# CH32V203CCT-WUI-R1-1v0.net
KiCad netlist of a schematic drawn in Altium Designer
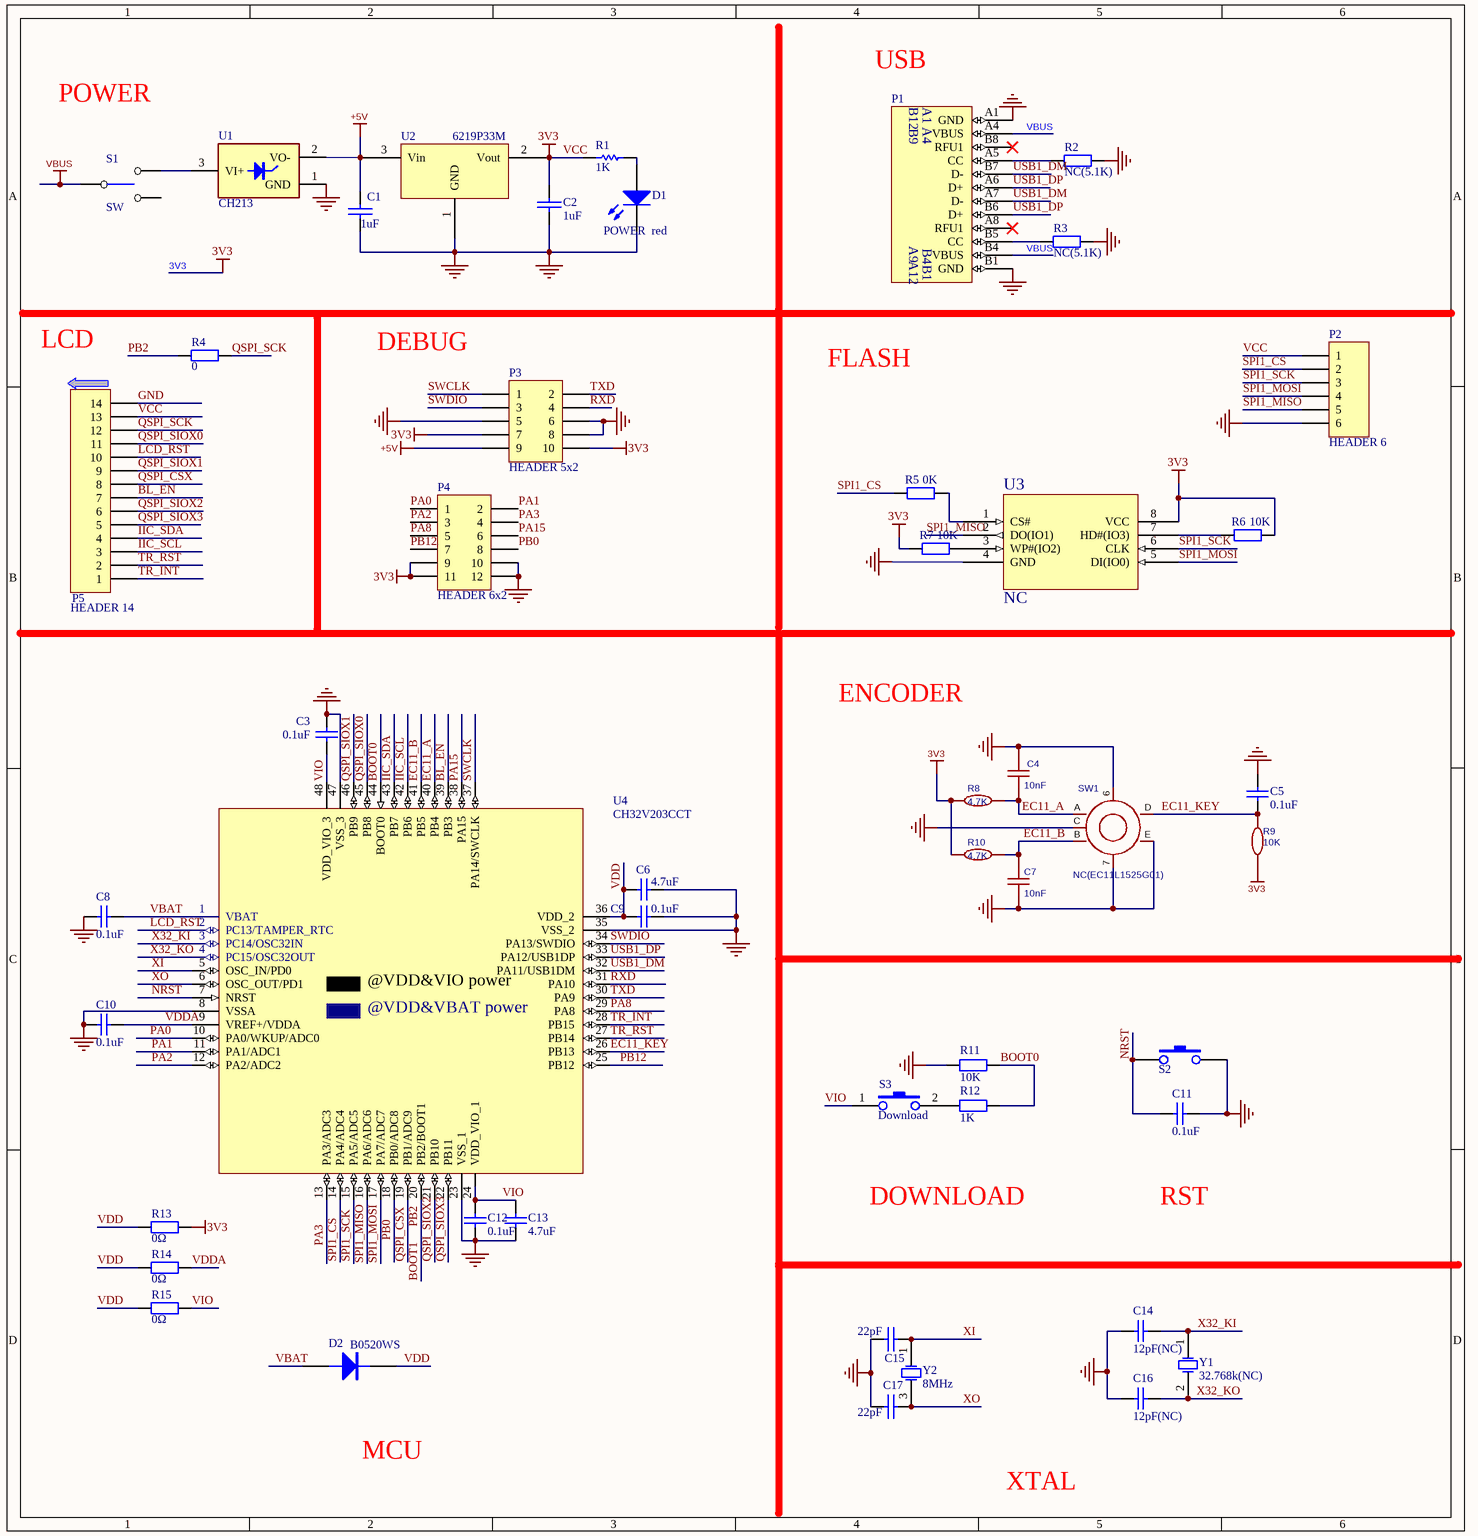
[diagram p0: CH32V203CCT-WUI-R1-1v0.SchDoc]

(export (version "E")
  (design (tool "Eeschema 10.0.6"))
  (components
    (comp (ref "C1")
      (value "1uF")
      (footprint "0402_C")
      (description "Capacitor")
      (libsource (lib "*") (part "CAP"))
    )
    (comp (ref "C2")
      (value "1uF")
      (footprint "0402_C")
      (description "Capacitor")
      (libsource (lib "*") (part "CAP"))
    )
    (comp (ref "C3")
      (value "0.1uF")
      (footprint "0402_C")
      (description "Capacitor")
      (fields (field (name "PUBLISHER") "Altium Limited"))
      (libsource (lib "*") (part "Cap"))
    )
    (comp (ref "C4")
      (value "10nF")
      (footprint "0402_C")
      (libsource (lib "altium-import") (part "root_1_CAP_0603_"))
    )
    (comp (ref "C5")
      (value "0.1uF")
      (footprint "0402_C")
      (description "Capacitor")
      (fields (field (name "PUBLISHER") "Altium Limited"))
      (libsource (lib "*") (part "Cap"))
    )
    (comp (ref "C6")
      (value "4.7uF")
      (footprint "0402_C")
      (description "Capacitor")
      (fields (field (name "PUBLISHER") "Altium Limited"))
      (libsource (lib "*") (part "Cap"))
    )
    (comp (ref "C7")
      (value "10nF")
      (footprint "0402_C")
      (libsource (lib "altium-import") (part "root_3_CAP_0603_"))
    )
    (comp (ref "C8")
      (value "0.1uF")
      (footprint "0402_C")
      (description "Capacitor")
      (fields (field (name "PUBLISHER") "Altium Limited"))
      (libsource (lib "*") (part "Cap"))
    )
    (comp (ref "C9")
      (value "0.1uF")
      (footprint "0402_C")
      (description "Capacitor")
      (fields (field (name "PUBLISHER") "Altium Limited"))
      (libsource (lib "*") (part "Cap"))
    )
    (comp (ref "C10")
      (value "0.1uF")
      (footprint "0402_C")
      (description "Capacitor")
      (fields (field (name "PUBLISHER") "Altium Limited"))
      (libsource (lib "*") (part "Cap"))
    )
    (comp (ref "C11")
      (value "0.1uF")
      (footprint "0402_C")
      (description "Capacitor")
      (fields (field (name "PUBLISHER") "Altium Limited"))
      (libsource (lib "*") (part "Cap"))
    )
    (comp (ref "C12")
      (value "0.1uF")
      (footprint "0402_C")
      (description "Capacitor")
      (fields (field (name "PUBLISHER") "Altium Limited"))
      (libsource (lib "*") (part "Cap"))
    )
    (comp (ref "C13")
      (value "4.7uF")
      (footprint "0402_C")
      (description "Capacitor")
      (fields (field (name "PUBLISHER") "Altium Limited"))
      (libsource (lib "*") (part "Cap"))
    )
    (comp (ref "C14")
      (value "12pF(NC)")
      (footprint "0402_C")
      (description "Capacitor")
      (fields (field (name "PUBLISHER") "Altium Limited"))
      (libsource (lib "*") (part "Cap"))
    )
    (comp (ref "C15")
      (value "22pF")
      (footprint "0402_C")
      (description "Capacitor")
      (libsource (lib "*") (part "CAP"))
    )
    (comp (ref "C16")
      (value "12pF(NC)")
      (footprint "0402_C")
      (description "Capacitor")
      (fields (field (name "PUBLISHER") "Altium Limited"))
      (libsource (lib "*") (part "Cap"))
    )
    (comp (ref "C17")
      (value "22pF")
      (footprint "0402_C")
      (description "Capacitor")
      (libsource (lib "*") (part "CAP"))
    )
    (comp (ref "D1")
      (value "POWER  red")
      (footprint "0603+")
      (description "Typical INFRARED GaAs LED")
      (fields (field (name "PUBLISHER") "Altium Limited"))
      (libsource (lib "*") (part "LED0"))
    )
    (comp (ref "D2")
      (value "B0520WS")
      (footprint "SOD-323")
      (description "Diode")
      (libsource (lib "*") (part "DIODE"))
    )
    (comp (ref "P1")
      (value "TYPE-C")
      (footprint "TYPE-C-Receptacle-2.0")
      (libsource (lib "*") (part "TYPE-C1"))
    )
    (comp (ref "P2")
      (value "HEADER 6")
      (footprint "SIP6-2.54mm")
      (description "Header, 6-Pin")
      (libsource (lib "wch_sch_others") (part "HEADER 6"))
    )
    (comp (ref "P3")
      (value "HEADER 5x2")
      (footprint "MYPCB:IDC10-2.54mm")
      (description "Header, 5-Pin, Dual row")
      (libsource (lib "wch_sch_others") (part "HEADER 5x2"))
    )
    (comp (ref "P4")
      (value "HEADER 6x2")
      (footprint "MYPCB:IDC12-2.54mm")
      (description "Header, 6-Pin, Dual row")
      (libsource (lib "wch_sch_others") (part "HEADER 6x2"))
    )
    (comp (ref "P5")
      (value "HEADER 14")
      (footprint "SIP14-2.54mm")
      (description "Header, 14-Pin")
      (libsource (lib "wch_sch_others") (part "HEADER 14"))
    )
    (comp (ref "R1")
      (value "1K")
      (footprint "0402")
      (description "Semiconductor Resistor")
      (fields (field (name "PUBLISHER") "Altium Limited"))
      (libsource (lib "*") (part "Res Semi"))
    )
    (comp (ref "R2")
      (value "NC(5.1K)")
      (footprint "0402")
      (description "Resistor")
      (libsource (lib "") (part "Res2_1"))
    )
    (comp (ref "R3")
      (value "NC(5.1K)")
      (footprint "0402")
      (description "Resistor")
      (libsource (lib "") (part "Res2_1"))
    )
    (comp (ref "R4")
      (value "0")
      (footprint "0402")
      (description "Resistor")
      (fields (field (name "PUBLISHER") "Altium Limited"))
      (libsource (lib "") (part "Res2_1"))
    )
    (comp (ref "R5")
      (value "0K")
      (footprint "0402")
      (description "Resistor")
      (fields (field (name "PUBLISHER") "Altium Limited"))
      (libsource (lib "*") (part "Res2"))
    )
    (comp (ref "R6")
      (value "10K")
      (footprint "0402")
      (description "Resistor")
      (fields (field (name "PUBLISHER") "Altium Limited"))
      (libsource (lib "*") (part "Res2"))
    )
    (comp (ref "R7")
      (value "10K")
      (footprint "0402")
      (description "Resistor")
      (fields (field (name "PUBLISHER") "Altium Limited"))
      (libsource (lib "*") (part "Res2"))
    )
    (comp (ref "R8")
      (value "4.7K")
      (footprint "0402")
      (libsource (lib "altium-import") (part "root_0_Res_0603_"))
    )
    (comp (ref "R9")
      (value "10K")
      (footprint "0402")
      (libsource (lib "altium-import") (part "root_3_Res_0603_"))
    )
    (comp (ref "R10")
      (value "4.7K")
      (footprint "0402")
      (libsource (lib "altium-import") (part "root_0_Res_0603_"))
    )
    (comp (ref "R11")
      (value "10K")
      (footprint "0402")
      (description "Resistor")
      (fields (field (name "PUBLISHER") "Altium Limited"))
      (libsource (lib "Miscellaneous Devices") (part "Res2"))
    )
    (comp (ref "R12")
      (value "1K")
      (footprint "0402")
      (description "Resistor")
      (fields (field (name "PUBLISHER") "Altium Limited"))
      (libsource (lib "Miscellaneous Devices") (part "Res2"))
    )
    (comp (ref "R13")
      (value "0Ω")
      (footprint "0402")
      (description "Resistor")
      (libsource (lib "Miscellaneous Devices") (part "Res2"))
    )
    (comp (ref "R14")
      (value "0Ω")
      (footprint "0402")
      (description "Resistor")
      (libsource (lib "Miscellaneous Devices") (part "Res2"))
    )
    (comp (ref "R15")
      (value "0Ω")
      (footprint "0402")
      (description "Resistor")
      (libsource (lib "Miscellaneous Devices") (part "Res2"))
    )
    (comp (ref "S1") (value "SW") (footprint "SW1") (libsource (lib "*") (part "SW")))
    (comp (ref "S2") (value "NRST") (footprint "贴片按键") (libsource (lib "*") (part "KEY")))
    (comp (ref "S3") (value "Download") (footprint "贴片按键") (libsource (lib "wch_sch_others") (part "KEY1")))
    (comp (ref "SW1")
      (value "NC(EC11L1525G01)")
      (footprint "SW-TH_ALPS_EC11L1525G01")
      (fields
        (field (name "MANUFACTURER") "ALPSALPINE(阿尔卑斯阿尔派)")
        (field (name "MANUFACTURERPART") "EC11L1525G01")
      )
      (libsource (lib "altium-import") (part "root_3_EC11L1525G01_"))
    )
    (comp (ref "U1")
      (value "CH213")
      (footprint "SOT-23-3")
      (description "Ideal Diode 5V*1A")
      (libsource (lib "CHXXX") (part "CH213E"))
    )
    (comp (ref "U2")
      (value "6219P33M")
      (footprint "SOT-23")
      (libsource (lib "wch_sch_others") (part "6219P33M"))
    )
    (comp (ref "U3")
      (value "NC")
      (footprint "SOIC-8_208mil")
      (libsource (lib "wch_sch_others") (part "W25Q32JV"))
    )
    (comp (ref "U4")
      (value "CH32V203CCT")
      (footprint "LQFP48")
      (description "RISC-V MCU, 192MHz, USB FS, PIOC, ADC, TKEY, 2*OPA, 2*CMP")
      (libsource (lib "CHXXX") (part "CH32V203CCT"))
    )
    (comp (ref "Y1")
      (value "32.768k(NC)")
      (footprint "FC-135")
      (description "Crystal Oscillator")
      (fields (field (name "PUBLISHER") "Altium Limited"))
      (libsource (lib "") (part "XTAL_1"))
    )
    (comp (ref "Y2")
      (value "8MHz")
      (footprint "XT3225")
      (description "Crystal Oscillator")
      (fields (field (name "PUBLISHER") "Altium Limited"))
      (libsource (lib "*") (part "XTAL"))
    )
  )
  (nets
    (net (code "1") (name "+5V") (class "Default")
      (node (ref "C1") (pin "1") (pinfunction "1_1") (pintype "passive"))
      (node (ref "P3") (pin "9") (pinfunction "9_9") (pintype "passive"))
      (node (ref "U1") (pin "2") (pinfunction "VO-_2") (pintype "power_in"))
      (node (ref "U2") (pin "3") (pinfunction "Vin_3") (pintype "passive"))
    )
    (net (code "2") (name "/BL_EN") (class "Default")
      (node (ref "P5") (pin "7") (pinfunction "7_7") (pintype "passive"))
      (node (ref "U4") (pin "39") (pinfunction "PB3_39") (pintype "bidirectional"))
    )
    (net (code "3") (name "/BOOT0") (class "Default")
      (node (ref "R11") (pin "1") (pinfunction "1_1") (pintype "passive"))
      (node (ref "R12") (pin "1") (pinfunction "1_1") (pintype "passive"))
      (node (ref "U4") (pin "44") (pinfunction "BOOT0_44") (pintype "input"))
    )
    (net (code "4") (name "/BOOT1") (class "Default")
      (node (ref "R4") (pin "1") (pinfunction "1_1") (pintype "passive"))
      (node (ref "U4") (pin "20") (pinfunction "PB2/BOOT1_20") (pintype "bidirectional"))
    )
    (net (code "5") (name "/EC11_A") (class "Default")
      (node (ref "C4") (pin "1") (pinfunction "1_1") (pintype "passive"))
      (node (ref "R8") (pin "2") (pinfunction "2_2") (pintype "passive"))
      (node (ref "SW1") (pin "A") (pinfunction "A_A") (pintype "passive"))
      (node (ref "U4") (pin "40") (pinfunction "PB4_40") (pintype "bidirectional"))
    )
    (net (code "6") (name "/EC11_B") (class "Default")
      (node (ref "C7") (pin "1") (pinfunction "1_1") (pintype "passive"))
      (node (ref "R10") (pin "2") (pinfunction "2_2") (pintype "passive"))
      (node (ref "SW1") (pin "B") (pinfunction "B_B") (pintype "passive"))
      (node (ref "U4") (pin "41") (pinfunction "PB5_41") (pintype "bidirectional"))
    )
    (net (code "7") (name "/EC11_KEY") (class "Default")
      (node (ref "C5") (pin "2") (pinfunction "2_2") (pintype "passive"))
      (node (ref "R9") (pin "1") (pinfunction "1_1") (pintype "passive"))
      (node (ref "SW1") (pin "D") (pinfunction "D_D") (pintype "passive"))
      (node (ref "U4") (pin "26") (pinfunction "PB13_26") (pintype "bidirectional"))
    )
    (net (code "8") (name "/IIC_SCL") (class "Default")
      (node (ref "P5") (pin "3") (pinfunction "3_3") (pintype "passive"))
      (node (ref "U4") (pin "42") (pinfunction "PB6_42") (pintype "bidirectional"))
    )
    (net (code "9") (name "/IIC_SDA") (class "Default")
      (node (ref "P5") (pin "4") (pinfunction "4_4") (pintype "passive"))
      (node (ref "U4") (pin "43") (pinfunction "PB7_43") (pintype "bidirectional"))
    )
    (net (code "10") (name "/LCD_RST") (class "Default")
      (node (ref "P5") (pin "10") (pinfunction "10_10") (pintype "passive"))
      (node (ref "U4") (pin "2") (pinfunction "PC13/TAMPER_RTC_2") (pintype "bidirectional"))
    )
    (net (code "11") (name "/NRST") (class "Default")
      (node (ref "C11") (pin "2") (pinfunction "2_2") (pintype "passive"))
      (node (ref "S2") (pin "1") (pinfunction "1_1") (pintype "passive"))
      (node (ref "U4") (pin "7") (pinfunction "NRST_7") (pintype "input"))
    )
    (net (code "12") (name "/PA0") (class "Default")
      (node (ref "P4") (pin "1") (pinfunction "1_1") (pintype "passive"))
      (node (ref "U4") (pin "10") (pinfunction "PA0/WKUP/ADC0_10") (pintype "bidirectional"))
    )
    (net (code "13") (name "/PA1") (class "Default")
      (node (ref "P4") (pin "2") (pinfunction "2_2") (pintype "passive"))
      (node (ref "U4") (pin "11") (pinfunction "PA1/ADC1_11") (pintype "bidirectional"))
    )
    (net (code "14") (name "/PA2") (class "Default")
      (node (ref "P4") (pin "3") (pinfunction "3_3") (pintype "passive"))
      (node (ref "U4") (pin "12") (pinfunction "PA2/ADC2_12") (pintype "bidirectional"))
    )
    (net (code "15") (name "/PA3") (class "Default")
      (node (ref "P4") (pin "4") (pinfunction "4_4") (pintype "passive"))
      (node (ref "U4") (pin "13") (pinfunction "PA3/ADC3_13") (pintype "bidirectional"))
    )
    (net (code "16") (name "/PA8") (class "Default")
      (node (ref "P4") (pin "5") (pinfunction "5_5") (pintype "passive"))
      (node (ref "U4") (pin "29") (pinfunction "PA8_29") (pintype "bidirectional"))
    )
    (net (code "17") (name "/PA15") (class "Default")
      (node (ref "P4") (pin "6") (pinfunction "6_6") (pintype "passive"))
      (node (ref "U4") (pin "38") (pinfunction "PA15_38") (pintype "bidirectional"))
    )
    (net (code "18") (name "/PB0") (class "Default")
      (node (ref "P4") (pin "8") (pinfunction "8_8") (pintype "passive"))
      (node (ref "U4") (pin "18") (pinfunction "PB0/ADC8_18") (pintype "bidirectional"))
    )
    (net (code "19") (name "/PB12") (class "Default")
      (node (ref "P4") (pin "7") (pinfunction "7_7") (pintype "passive"))
      (node (ref "U4") (pin "25") (pinfunction "PB12_25") (pintype "bidirectional"))
    )
    (net (code "20") (name "/QSPI_CSX") (class "Default")
      (node (ref "P5") (pin "8") (pinfunction "8_8") (pintype "passive"))
      (node (ref "U4") (pin "19") (pinfunction "PB1/ADC9_19") (pintype "bidirectional"))
    )
    (net (code "21") (name "/QSPI_SCK") (class "Default")
      (node (ref "P5") (pin "12") (pinfunction "12_12") (pintype "passive"))
      (node (ref "R4") (pin "2") (pinfunction "2_2") (pintype "passive"))
    )
    (net (code "22") (name "/QSPI_SIOX0") (class "Default")
      (node (ref "P5") (pin "11") (pinfunction "11_11") (pintype "passive"))
      (node (ref "U4") (pin "45") (pinfunction "PB8_45") (pintype "bidirectional"))
    )
    (net (code "23") (name "/QSPI_SIOX1") (class "Default")
      (node (ref "P5") (pin "9") (pinfunction "9_9") (pintype "passive"))
      (node (ref "U4") (pin "46") (pinfunction "PB9_46") (pintype "bidirectional"))
    )
    (net (code "24") (name "/QSPI_SIOX2") (class "Default")
      (node (ref "P5") (pin "6") (pinfunction "6_6") (pintype "passive"))
      (node (ref "U4") (pin "21") (pinfunction "PB10_21") (pintype "bidirectional"))
    )
    (net (code "25") (name "/QSPI_SIOX3") (class "Default")
      (node (ref "P5") (pin "5") (pinfunction "5_5") (pintype "passive"))
      (node (ref "U4") (pin "22") (pinfunction "PB11_22") (pintype "bidirectional"))
    )
    (net (code "26") (name "/RXD") (class "Default")
      (node (ref "P3") (pin "4") (pinfunction "4_4") (pintype "passive"))
      (node (ref "U4") (pin "31") (pinfunction "PA10_31") (pintype "bidirectional"))
    )
    (net (code "27") (name "/SPI1_CS") (class "Default")
      (node (ref "P2") (pin "2") (pinfunction "2_2") (pintype "passive"))
      (node (ref "R5") (pin "1") (pinfunction "1_1") (pintype "passive"))
      (node (ref "U4") (pin "14") (pinfunction "PA4/ADC4_14") (pintype "bidirectional"))
    )
    (net (code "28") (name "/SPI1_MISO") (class "Default")
      (node (ref "P2") (pin "5") (pinfunction "5_5") (pintype "passive"))
      (node (ref "U3") (pin "2") (pinfunction "DO(IO1)_2") (pintype "output"))
      (node (ref "U4") (pin "16") (pinfunction "PA6/ADC6_16") (pintype "bidirectional"))
    )
    (net (code "29") (name "/SPI1_MOSI") (class "Default")
      (node (ref "P2") (pin "4") (pinfunction "4_4") (pintype "passive"))
      (node (ref "U3") (pin "5") (pinfunction "DI(IO0)_5") (pintype "input"))
      (node (ref "U4") (pin "17") (pinfunction "PA7/ADC7_17") (pintype "bidirectional"))
    )
    (net (code "30") (name "/SPI1_SCK") (class "Default")
      (node (ref "P2") (pin "3") (pinfunction "3_3") (pintype "passive"))
      (node (ref "U3") (pin "6") (pinfunction "CLK_6") (pintype "input"))
      (node (ref "U4") (pin "15") (pinfunction "PA5/ADC5_15") (pintype "bidirectional"))
    )
    (net (code "31") (name "/SWCLK") (class "Default")
      (node (ref "P3") (pin "1") (pinfunction "1_1") (pintype "passive"))
      (node (ref "U4") (pin "37") (pinfunction "PA14/SWCLK_37") (pintype "bidirectional"))
    )
    (net (code "32") (name "/SWDIO") (class "Default")
      (node (ref "P3") (pin "3") (pinfunction "3_3") (pintype "passive"))
      (node (ref "U4") (pin "34") (pinfunction "PA13/SWDIO_34") (pintype "bidirectional"))
    )
    (net (code "33") (name "/TR_INT") (class "Default")
      (node (ref "P5") (pin "1") (pinfunction "1_1") (pintype "passive"))
      (node (ref "U4") (pin "28") (pinfunction "PB15_28") (pintype "bidirectional"))
    )
    (net (code "34") (name "/TR_RST") (class "Default")
      (node (ref "P5") (pin "2") (pinfunction "2_2") (pintype "passive"))
      (node (ref "U4") (pin "27") (pinfunction "PB14_27") (pintype "bidirectional"))
    )
    (net (code "35") (name "/TXD") (class "Default")
      (node (ref "P3") (pin "2") (pinfunction "2_2") (pintype "passive"))
      (node (ref "U4") (pin "30") (pinfunction "PA9_30") (pintype "bidirectional"))
    )
    (net (code "36") (name "/USB1_DM") (class "Default")
      (node (ref "P1") (pin "A7") (pinfunction "D-_A7") (pintype "bidirectional"))
      (node (ref "P1") (pin "B7") (pinfunction "D-_B7") (pintype "bidirectional"))
      (node (ref "U4") (pin "32") (pinfunction "PA11/USB1DM_32") (pintype "bidirectional"))
    )
    (net (code "37") (name "/USB1_DP") (class "Default")
      (node (ref "P1") (pin "A6") (pinfunction "D+_A6") (pintype "bidirectional"))
      (node (ref "P1") (pin "B6") (pinfunction "D+_B6") (pintype "bidirectional"))
      (node (ref "U4") (pin "33") (pinfunction "PA12/USB1DP_33") (pintype "bidirectional"))
    )
    (net (code "38") (name "/VBAT") (class "Default")
      (node (ref "C8") (pin "1") (pinfunction "1_1") (pintype "passive"))
      (node (ref "D2") (pin "1") (pinfunction "A_1") (pintype "passive"))
      (node (ref "U4") (pin "1") (pinfunction "VBAT_1") (pintype "power_in"))
    )
    (net (code "39") (name "/VDD") (class "Default")
      (node (ref "C6") (pin "2") (pinfunction "2_2") (pintype "passive"))
      (node (ref "C9") (pin "2") (pinfunction "2_2") (pintype "passive"))
      (node (ref "D2") (pin "2") (pinfunction "K_2") (pintype "passive"))
      (node (ref "R13") (pin "2") (pinfunction "2_2") (pintype "passive"))
      (node (ref "R14") (pin "2") (pinfunction "2_2") (pintype "passive"))
      (node (ref "R15") (pin "2") (pinfunction "2_2") (pintype "passive"))
      (node (ref "U4") (pin "36") (pinfunction "VDD_2_36") (pintype "power_in"))
    )
    (net (code "40") (name "/VDDA") (class "Default")
      (node (ref "C10") (pin "1") (pinfunction "1_1") (pintype "passive"))
      (node (ref "R14") (pin "1") (pinfunction "1_1") (pintype "passive"))
      (node (ref "U4") (pin "9") (pinfunction "VREF+/VDDA_9") (pintype "power_in"))
    )
    (net (code "41") (name "/VIO") (class "Default")
      (node (ref "C12") (pin "2") (pinfunction "2_2") (pintype "passive"))
      (node (ref "C13") (pin "1") (pinfunction "1_1") (pintype "passive"))
      (node (ref "C3") (pin "2") (pinfunction "2_2") (pintype "passive"))
      (node (ref "R15") (pin "1") (pinfunction "1_1") (pintype "passive"))
      (node (ref "S3") (pin "1") (pinfunction "1_1") (pintype "passive"))
      (node (ref "U4") (pin "24") (pinfunction "VDD_VIO_1_24") (pintype "power_in"))
      (node (ref "U4") (pin "48") (pinfunction "VDD_VIO_3_48") (pintype "power_in"))
    )
    (net (code "42") (name "/X32_KI") (class "Default")
      (node (ref "C14") (pin "1") (pinfunction "1_1") (pintype "passive"))
      (node (ref "U4") (pin "3") (pinfunction "PC14/OSC32IN_3") (pintype "bidirectional"))
      (node (ref "Y1") (pin "1") (pinfunction "OSC1_1") (pintype "passive"))
    )
    (net (code "43") (name "/X32_KO") (class "Default")
      (node (ref "C16") (pin "1") (pinfunction "1_1") (pintype "passive"))
      (node (ref "U4") (pin "4") (pinfunction "PC15/OSC32OUT_4") (pintype "bidirectional"))
      (node (ref "Y1") (pin "2") (pinfunction "OSC2_2") (pintype "passive"))
    )
    (net (code "44") (name "/XI") (class "Default")
      (node (ref "C15") (pin "2") (pinfunction "2_2") (pintype "passive"))
      (node (ref "U4") (pin "5") (pinfunction "OSC_IN/PD0_5") (pintype "bidirectional"))
      (node (ref "Y2") (pin "1") (pinfunction "OSC1_1") (pintype "passive"))
    )
    (net (code "45") (name "/XO") (class "Default")
      (node (ref "C17") (pin "2") (pinfunction "2_2") (pintype "passive"))
      (node (ref "U4") (pin "6") (pinfunction "OSC_OUT/PD1_6") (pintype "bidirectional"))
      (node (ref "Y2") (pin "3") (pinfunction "OSC2_3") (pintype "passive"))
    )
    (net (code "46") (name "3V3") (class "Default")
      (node (ref "C2") (pin "1") (pinfunction "1_1") (pintype "passive"))
      (node (ref "P2") (pin "1") (pinfunction "1_1") (pintype "passive"))
      (node (ref "P3") (pin "10") (pinfunction "10_10") (pintype "passive"))
      (node (ref "P3") (pin "7") (pinfunction "7_7") (pintype "passive"))
      (node (ref "P4") (pin "11") (pinfunction "11_11") (pintype "passive"))
      (node (ref "P4") (pin "9") (pinfunction "9_9") (pintype "passive"))
      (node (ref "P5") (pin "13") (pinfunction "13_13") (pintype "passive"))
      (node (ref "R1") (pin "2") (pinfunction "2_2") (pintype "passive"))
      (node (ref "R10") (pin "1") (pinfunction "1_1") (pintype "passive"))
      (node (ref "R13") (pin "1") (pinfunction "1_1") (pintype "passive"))
      (node (ref "R6") (pin "2") (pinfunction "2_2") (pintype "passive"))
      (node (ref "R7") (pin "1") (pinfunction "1_1") (pintype "passive"))
      (node (ref "R8") (pin "1") (pinfunction "1_1") (pintype "passive"))
      (node (ref "R9") (pin "2") (pinfunction "2_2") (pintype "passive"))
      (node (ref "U2") (pin "2") (pinfunction "Vout_2") (pintype "passive"))
      (node (ref "U3") (pin "8") (pinfunction "VCC_8") (pintype "power_in"))
    )
    (net (code "47") (name "GND") (class "Default")
      (node (ref "C1") (pin "2") (pinfunction "2_2") (pintype "passive"))
      (node (ref "C10") (pin "2") (pinfunction "2_2") (pintype "passive"))
      (node (ref "C11") (pin "1") (pinfunction "1_1") (pintype "passive"))
      (node (ref "C12") (pin "1") (pinfunction "1_1") (pintype "passive"))
      (node (ref "C13") (pin "2") (pinfunction "2_2") (pintype "passive"))
      (node (ref "C14") (pin "2") (pinfunction "2_2") (pintype "passive"))
      (node (ref "C15") (pin "1") (pinfunction "1_1") (pintype "passive"))
      (node (ref "C16") (pin "2") (pinfunction "2_2") (pintype "passive"))
      (node (ref "C17") (pin "1") (pinfunction "1_1") (pintype "passive"))
      (node (ref "C2") (pin "2") (pinfunction "2_2") (pintype "passive"))
      (node (ref "C3") (pin "1") (pinfunction "1_1") (pintype "passive"))
      (node (ref "C4") (pin "2") (pinfunction "2_2") (pintype "passive"))
      (node (ref "C5") (pin "1") (pinfunction "1_1") (pintype "passive"))
      (node (ref "C6") (pin "1") (pinfunction "1_1") (pintype "passive"))
      (node (ref "C7") (pin "2") (pinfunction "2_2") (pintype "passive"))
      (node (ref "C8") (pin "2") (pinfunction "2_2") (pintype "passive"))
      (node (ref "C9") (pin "1") (pinfunction "1_1") (pintype "passive"))
      (node (ref "D1") (pin "2") (pinfunction "K_2") (pintype "passive"))
      (node (ref "P1") (pin "A1") (pinfunction "GND_A1") (pintype "bidirectional"))
      (node (ref "P1") (pin "B1") (pinfunction "GND_B1") (pintype "bidirectional"))
      (node (ref "P2") (pin "6") (pinfunction "6_6") (pintype "passive"))
      (node (ref "P3") (pin "5") (pinfunction "5_5") (pintype "passive"))
      (node (ref "P3") (pin "6") (pinfunction "6_6") (pintype "passive"))
      (node (ref "P3") (pin "8") (pinfunction "8_8") (pintype "passive"))
      (node (ref "P4") (pin "10") (pinfunction "10_10") (pintype "passive"))
      (node (ref "P4") (pin "12") (pinfunction "12_12") (pintype "passive"))
      (node (ref "P5") (pin "14") (pinfunction "14_14") (pintype "passive"))
      (node (ref "R11") (pin "2") (pinfunction "2_2") (pintype "passive"))
      (node (ref "R2") (pin "2") (pinfunction "2_2") (pintype "passive"))
      (node (ref "R3") (pin "2") (pinfunction "2_2") (pintype "passive"))
      (node (ref "S2") (pin "2") (pinfunction "2_2") (pintype "passive"))
      (node (ref "SW1") (pin "6") (pinfunction "EH_6") (pintype "passive"))
      (node (ref "SW1") (pin "7") (pinfunction "EH_7") (pintype "passive"))
      (node (ref "SW1") (pin "C") (pinfunction "C_C") (pintype "passive"))
      (node (ref "SW1") (pin "E") (pinfunction "E_E") (pintype "passive"))
      (node (ref "U1") (pin "1") (pinfunction "GND_1") (pintype "power_in"))
      (node (ref "U2") (pin "1") (pinfunction "GND_1") (pintype "passive"))
      (node (ref "U3") (pin "4") (pinfunction "GND_4") (pintype "power_in"))
      (node (ref "U4") (pin "23") (pinfunction "VSS_1_23") (pintype "power_in"))
      (node (ref "U4") (pin "35") (pinfunction "VSS_2_35") (pintype "power_in"))
      (node (ref "U4") (pin "47") (pinfunction "VSS_3_47") (pintype "power_in"))
      (node (ref "U4") (pin "8") (pinfunction "VSSA_8") (pintype "power_in"))
    )
    (net (code "48") (name "Net-(D1-A)") (class "Default")
      (node (ref "D1") (pin "1") (pinfunction "A_1") (pintype "passive"))
      (node (ref "R1") (pin "1") (pinfunction "1_1") (pintype "passive"))
    )
    (net (code "49") (name "Net-(P1-CC-PadA5)") (class "Default")
      (node (ref "P1") (pin "A5") (pinfunction "CC_A5") (pintype "bidirectional"))
      (node (ref "R2") (pin "1") (pinfunction "1_1") (pintype "passive"))
    )
    (net (code "50") (name "Net-(P1-CC-PadB5)") (class "Default")
      (node (ref "P1") (pin "B5") (pinfunction "CC_B5") (pintype "bidirectional"))
      (node (ref "R3") (pin "1") (pinfunction "1_1") (pintype "passive"))
    )
    (net (code "51") (name "Net-(R12-Pad2)") (class "Default")
      (node (ref "R12") (pin "2") (pinfunction "2_2") (pintype "passive"))
      (node (ref "S3") (pin "2") (pinfunction "2_2") (pintype "passive"))
    )
    (net (code "52") (name "Net-(U1-VI+)") (class "Default")
      (node (ref "S1") (pin "3") (pinfunction "3_3") (pintype "passive"))
      (node (ref "U1") (pin "3") (pinfunction "VI+_3") (pintype "power_in"))
    )
    (net (code "53") (name "Net-(U3-CS#)") (class "Default")
      (node (ref "R5") (pin "2") (pinfunction "2_2") (pintype "passive"))
      (node (ref "U3") (pin "1") (pinfunction "CS#_1") (pintype "input"))
    )
    (net (code "54") (name "Net-(U3-HD#(IO3))") (class "Default")
      (node (ref "R6") (pin "1") (pinfunction "1_1") (pintype "passive"))
      (node (ref "U3") (pin "7") (pinfunction "HD#(IO3)_7") (pintype "power_in"))
    )
    (net (code "55") (name "Net-(U3-WP#(IO2))") (class "Default")
      (node (ref "R7") (pin "2") (pinfunction "2_2") (pintype "passive"))
      (node (ref "U3") (pin "3") (pinfunction "WP#(IO2)_3") (pintype "input"))
    )
    (net (code "56") (name "VBUS") (class "Default")
      (node (ref "P1") (pin "A4") (pinfunction "VBUS_A4") (pintype "bidirectional"))
      (node (ref "P1") (pin "B4") (pinfunction "VBUS_B4") (pintype "bidirectional"))
      (node (ref "S1") (pin "1") (pinfunction "1_1") (pintype "passive"))
    )
    (net (code "57") (name "unconnected-(P1-RFU1-PadA8)") (class "Default")
      (node (ref "P1") (pin "A8") (pinfunction "RFU1_A8") (pintype "bidirectional+no_connect"))
    )
    (net (code "58") (name "unconnected-(P1-RFU1-PadB8)") (class "Default")
      (node (ref "P1") (pin "B8") (pinfunction "RFU1_B8") (pintype "bidirectional+no_connect"))
    )
    (net (code "59") (name "unconnected-(S1-Pad2)") (class "Default")
      (node (ref "S1") (pin "2") (pinfunction "2_2") (pintype "passive"))
    )
  )
)
